# Chip_Inputs.net
KiCad netlist of a schematic drawn in Altium Designer
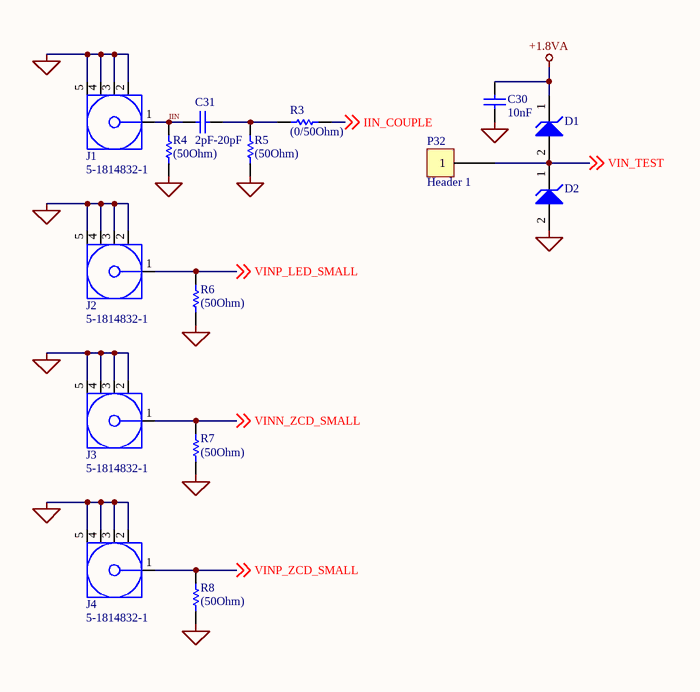
[diagram p0: Chip_Inputs.SchDoc]

(export (version "E")
  (design (tool "Eeschema 10.0.6"))
  (components
    (comp (ref "C30")
      (value "10nF")
      (footprint "CAPC1608X90X35ML10T15")
      (description "0603")
      (fields (field (name "MANUFACTURER") "Murata"))
      (libsource (lib "Altium Content Vault") (part "CAP-NP-2"))
    )
    (comp (ref "C31")
      (value "2pF-20pF")
      (footprint "CAPC1608X90X35ML10T15")
      (description "0603")
      (fields (field (name "MANUFACTURER") "Murata"))
      (libsource (lib "Altium Content Vault") (part "CAP-NP-2"))
    )
    (comp (ref "D1")
      (value "~")
      (footprint "ONSC-SOD-123-2-425-04_V")
      (description "Zener Voltage Regulator, 2-Pin SOD-123, Pb-Free, Tape and Reel")
      (fields (field (name "MANUFACTURER") "On Semiconductor") (field (name "PARTNUMBER") "MMSZ4679T1G"))
      (libsource (lib "Altium Content Vault") (part "ONSC-K1A2-2"))
    )
    (comp (ref "D2")
      (value "~")
      (footprint "ONSC-SOD-123-2-425-04_V")
      (description "Zener Voltage Regulator, 2-Pin SOD-123, Pb-Free, Tape and Reel")
      (fields (field (name "MANUFACTURER") "On Semiconductor") (field (name "PARTNUMBER") "MMSZ4679T1G"))
      (libsource (lib "Altium Content Vault") (part "ONSC-K1A2-2"))
    )
    (comp (ref "J1")
      (value "5-1814832-1")
      (footprint "TECO-5-1814832-1_V")
      (fields (field (name "MANUFACTURER") "TE Connectivity"))
      (libsource (lib "Altium Content Vault") (part "CN-S-4F-RF5"))
    )
    (comp (ref "J2")
      (value "5-1814832-1")
      (footprint "TECO-5-1814832-1_V")
      (fields (field (name "MANUFACTURER") "TE Connectivity"))
      (libsource (lib "Altium Content Vault") (part "CN-S-4F-RF5"))
    )
    (comp (ref "J3")
      (value "5-1814832-1")
      (footprint "TECO-5-1814832-1_V")
      (fields (field (name "MANUFACTURER") "TE Connectivity"))
      (libsource (lib "Altium Content Vault") (part "CN-S-4F-RF5"))
    )
    (comp (ref "J4")
      (value "5-1814832-1")
      (footprint "TECO-5-1814832-1_V")
      (fields (field (name "MANUFACTURER") "TE Connectivity"))
      (libsource (lib "Altium Content Vault") (part "CN-S-4F-RF5"))
    )
    (comp (ref "P32") (value "Header 1") (footprint "Header1") (libsource (lib "intlib") (part "Header 1")))
    (comp (ref "R3")
      (value "(0/50Ohm)")
      (footprint "RESC1609X50X30NL8T20")
      (description "0603")
      (fields (field (name "MANUFACTURER") "Vishay Semiconductor"))
      (libsource (lib "Altium Content Vault") (part "RES-2"))
    )
    (comp (ref "R4")
      (value "(50Ohm)")
      (footprint "RESC1609X50X30NL8T20")
      (description "0603")
      (fields (field (name "MANUFACTURER") "Vishay Semiconductor"))
      (libsource (lib "Altium Content Vault") (part "RES-2"))
    )
    (comp (ref "R5")
      (value "(50Ohm)")
      (footprint "RESC1609X50X30NL8T20")
      (description "0603")
      (fields (field (name "MANUFACTURER") "Vishay Semiconductor"))
      (libsource (lib "Altium Content Vault") (part "RES-2"))
    )
    (comp (ref "R6")
      (value "(50Ohm)")
      (footprint "RESC1609X50X30NL8T20")
      (description "0603")
      (fields (field (name "MANUFACTURER") "Vishay Semiconductor"))
      (libsource (lib "Altium Content Vault") (part "RES-2"))
    )
    (comp (ref "R7")
      (value "(50Ohm)")
      (footprint "RESC1609X50X30NL8T20")
      (description "0603")
      (fields (field (name "MANUFACTURER") "Vishay Semiconductor"))
      (libsource (lib "Altium Content Vault") (part "RES-2"))
    )
    (comp (ref "R8")
      (value "(50Ohm)")
      (footprint "RESC1609X50X30NL8T20")
      (description "0603")
      (fields (field (name "MANUFACTURER") "Vishay Semiconductor"))
      (libsource (lib "Altium Content Vault") (part "RES-2"))
    )
  )
  (nets
    (net (code "1") (name "+1.8VA") (class "Default")
      (node (ref "C30") (pin "2") (pinfunction "2_2") (pintype "passive"))
      (node (ref "D1") (pin "1") (pinfunction "K_1") (pintype "passive"))
    )
    (net (code "2") (name "/IIN") (class "Default")
      (node (ref "C31") (pin "2") (pinfunction "2_2") (pintype "passive"))
      (node (ref "J1") (pin "1") (pinfunction "1_1") (pintype "passive"))
      (node (ref "R4") (pin "2") (pinfunction "2_2") (pintype "passive"))
    )
    (net (code "3") (name "GND") (class "Default")
      (node (ref "C30") (pin "1") (pinfunction "1_1") (pintype "passive"))
      (node (ref "D2") (pin "2") (pinfunction "A_2") (pintype "passive"))
      (node (ref "J1") (pin "2") (pinfunction "2_2") (pintype "passive"))
      (node (ref "J1") (pin "3") (pinfunction "3_3") (pintype "passive"))
      (node (ref "J1") (pin "4") (pinfunction "4_4") (pintype "passive"))
      (node (ref "J1") (pin "5") (pinfunction "5_5") (pintype "passive"))
      (node (ref "J2") (pin "2") (pinfunction "2_2") (pintype "passive"))
      (node (ref "J2") (pin "3") (pinfunction "3_3") (pintype "passive"))
      (node (ref "J2") (pin "4") (pinfunction "4_4") (pintype "passive"))
      (node (ref "J2") (pin "5") (pinfunction "5_5") (pintype "passive"))
      (node (ref "J3") (pin "2") (pinfunction "2_2") (pintype "passive"))
      (node (ref "J3") (pin "3") (pinfunction "3_3") (pintype "passive"))
      (node (ref "J3") (pin "4") (pinfunction "4_4") (pintype "passive"))
      (node (ref "J3") (pin "5") (pinfunction "5_5") (pintype "passive"))
      (node (ref "J4") (pin "2") (pinfunction "2_2") (pintype "passive"))
      (node (ref "J4") (pin "3") (pinfunction "3_3") (pintype "passive"))
      (node (ref "J4") (pin "4") (pinfunction "4_4") (pintype "passive"))
      (node (ref "J4") (pin "5") (pinfunction "5_5") (pintype "passive"))
      (node (ref "R4") (pin "1") (pinfunction "1_1") (pintype "passive"))
      (node (ref "R5") (pin "1") (pinfunction "1_1") (pintype "passive"))
      (node (ref "R6") (pin "1") (pinfunction "1_1") (pintype "passive"))
      (node (ref "R7") (pin "1") (pinfunction "1_1") (pintype "passive"))
      (node (ref "R8") (pin "1") (pinfunction "1_1") (pintype "passive"))
    )
    (net (code "4") (name "IIN_COUPLE") (class "Default")
      (node (ref "R3") (pin "1") (pinfunction "1_1") (pintype "passive"))
    )
    (net (code "5") (name "Net-(C31-Pad1)") (class "Default")
      (node (ref "C31") (pin "1") (pinfunction "1_1") (pintype "passive"))
      (node (ref "R3") (pin "2") (pinfunction "2_2") (pintype "passive"))
      (node (ref "R5") (pin "2") (pinfunction "2_2") (pintype "passive"))
    )
    (net (code "6") (name "VINN_ZCD_SMALL") (class "Default")
      (node (ref "J3") (pin "1") (pinfunction "1_1") (pintype "passive"))
      (node (ref "R7") (pin "2") (pinfunction "2_2") (pintype "passive"))
    )
    (net (code "7") (name "VINP_LED_SMALL") (class "Default")
      (node (ref "J2") (pin "1") (pinfunction "1_1") (pintype "passive"))
      (node (ref "R6") (pin "2") (pinfunction "2_2") (pintype "passive"))
    )
    (net (code "8") (name "VINP_ZCD_SMALL") (class "Default")
      (node (ref "J4") (pin "1") (pinfunction "1_1") (pintype "passive"))
      (node (ref "R8") (pin "2") (pinfunction "2_2") (pintype "passive"))
    )
    (net (code "9") (name "VIN_TEST") (class "Default")
      (node (ref "D1") (pin "2") (pinfunction "A_2") (pintype "passive"))
      (node (ref "D2") (pin "1") (pinfunction "K_1") (pintype "passive"))
      (node (ref "P32") (pin "1") (pinfunction "1_1") (pintype "passive"))
    )
  )
)
